# delay_calibrator.net
KiCad netlist of a schematic drawn in EAGLE
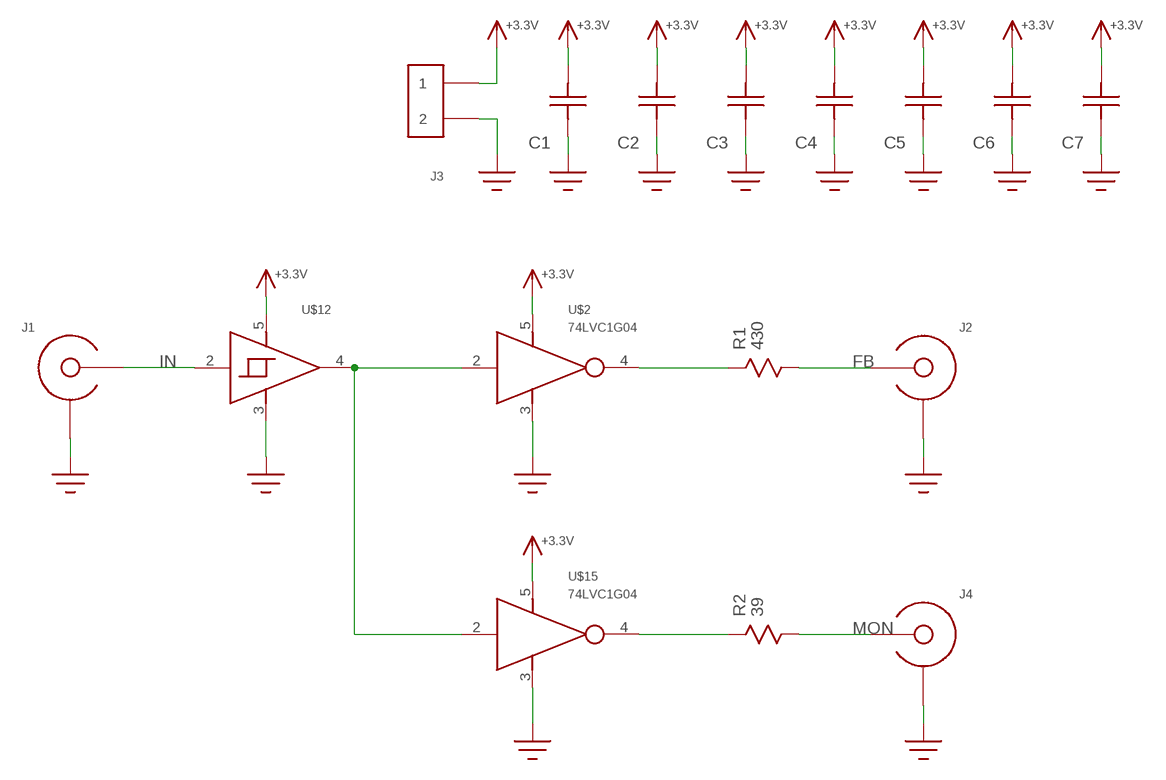
[diagram p0: schematic, sheet 1]

(export (version "E")
  (design (tool "Eeschema 10.0.6"))
  (components
    (comp (ref "C1")
      (value "C1206")
      (footprint "eagle-import:1206")
      (libsource (lib "eagle-import") (part "C1206"))
    )
    (comp (ref "C2")
      (value "C0603")
      (footprint "eagle-import:C0603")
      (libsource (lib "eagle-import") (part "C0603"))
    )
    (comp (ref "C3")
      (value "C0603")
      (footprint "eagle-import:C0603")
      (libsource (lib "eagle-import") (part "C0603"))
    )
    (comp (ref "C4")
      (value "C0603")
      (footprint "eagle-import:C0603")
      (libsource (lib "eagle-import") (part "C0603"))
    )
    (comp (ref "C5")
      (value "C0603")
      (footprint "eagle-import:C0603")
      (libsource (lib "eagle-import") (part "C0603"))
    )
    (comp (ref "C6")
      (value "C0603")
      (footprint "eagle-import:C0603")
      (libsource (lib "eagle-import") (part "C0603"))
    )
    (comp (ref "C7")
      (value "C0603")
      (footprint "eagle-import:C0603")
      (libsource (lib "eagle-import") (part "C0603"))
    )
    (comp (ref "J1")
      (value "EDGE_LAUNCH_JACK")
      (footprint "eagle-import:EDGE_LAUNCH_RF_CON")
      (libsource (lib "eagle-import") (part "EDGE_LAUNCH_JACK"))
    )
    (comp (ref "J2")
      (value "EDGE_LAUNCH_JACK")
      (footprint "eagle-import:EDGE_LAUNCH_RF_CON")
      (libsource (lib "eagle-import") (part "EDGE_LAUNCH_JACK"))
    )
    (comp (ref "J3")
      (value "HEADER_2PIN")
      (footprint "eagle-import:HEADER_2PIN")
      (libsource (lib "eagle-import") (part "HEADER_2PIN"))
    )
    (comp (ref "J4")
      (value "EDGE_LAUNCH_JACK")
      (footprint "eagle-import:EDGE_LAUNCH_RF_CON")
      (libsource (lib "eagle-import") (part "EDGE_LAUNCH_JACK"))
    )
    (comp (ref "R1")
      (value "430")
      (footprint "eagle-import:R0603")
      (libsource (lib "eagle-import") (part "R0603"))
    )
    (comp (ref "R2")
      (value "39")
      (footprint "eagle-import:R0603")
      (libsource (lib "eagle-import") (part "R0603"))
    )
    (comp (ref "U$2")
      (value "74LVC1G04")
      (footprint "eagle-import:SOT23-5")
      (libsource (lib "eagle-import") (part "74LVC1G04"))
    )
    (comp (ref "U$12")
      (value "74LVC1G17")
      (footprint "eagle-import:SOT23-5")
      (libsource (lib "eagle-import") (part "74LVC1G17"))
    )
    (comp (ref "U$15")
      (value "74LVC1G04")
      (footprint "eagle-import:SOT23-5")
      (libsource (lib "eagle-import") (part "74LVC1G04"))
    )
  )
  (nets
    (net (code "1") (name "+3.3V") (class "Default")
      (node (ref "C1") (pin "P$1") (pinfunction "P$1_P$1") (pintype "bidirectional"))
      (node (ref "C2") (pin "P$1") (pinfunction "P$1_P$1") (pintype "bidirectional"))
      (node (ref "C3") (pin "P$1") (pinfunction "P$1_P$1") (pintype "bidirectional"))
      (node (ref "C4") (pin "P$1") (pinfunction "P$1_P$1") (pintype "bidirectional"))
      (node (ref "C5") (pin "P$1") (pinfunction "P$1_P$1") (pintype "bidirectional"))
      (node (ref "C6") (pin "P$1") (pinfunction "P$1_P$1") (pintype "bidirectional"))
      (node (ref "C7") (pin "P$1") (pinfunction "P$1_P$1") (pintype "bidirectional"))
      (node (ref "J3") (pin "1") (pinfunction "1_1") (pintype "bidirectional"))
      (node (ref "U$12") (pin "5") (pinfunction "VCC_5") (pintype "bidirectional"))
      (node (ref "U$15") (pin "5") (pinfunction "VCC_5") (pintype "bidirectional"))
      (node (ref "U$2") (pin "5") (pinfunction "VCC_5") (pintype "bidirectional"))
    )
    (net (code "2") (name "/FB") (class "Default")
      (node (ref "J2") (pin "CENTER") (pinfunction "CENTER_CENTER") (pintype "bidirectional"))
      (node (ref "R1") (pin "P$2") (pinfunction "P$4_P$2") (pintype "bidirectional"))
    )
    (net (code "3") (name "/IN") (class "Default")
      (node (ref "J1") (pin "CENTER") (pinfunction "CENTER_CENTER") (pintype "bidirectional"))
      (node (ref "U$12") (pin "2") (pinfunction "IN_2") (pintype "bidirectional"))
    )
    (net (code "4") (name "/MON") (class "Default")
      (node (ref "J4") (pin "CENTER") (pinfunction "CENTER_CENTER") (pintype "bidirectional"))
      (node (ref "R2") (pin "P$2") (pinfunction "P$4_P$2") (pintype "bidirectional"))
    )
    (net (code "5") (name "GND") (class "Default")
      (node (ref "C1") (pin "P$2") (pinfunction "P$2_P$2") (pintype "bidirectional"))
      (node (ref "C2") (pin "P$2") (pinfunction "P$2_P$2") (pintype "bidirectional"))
      (node (ref "C3") (pin "P$2") (pinfunction "P$2_P$2") (pintype "bidirectional"))
      (node (ref "C4") (pin "P$2") (pinfunction "P$2_P$2") (pintype "bidirectional"))
      (node (ref "C5") (pin "P$2") (pinfunction "P$2_P$2") (pintype "bidirectional"))
      (node (ref "C6") (pin "P$2") (pinfunction "P$2_P$2") (pintype "bidirectional"))
      (node (ref "C7") (pin "P$2") (pinfunction "P$2_P$2") (pintype "bidirectional"))
      (node (ref "J1") (pin "GND@1") (pinfunction "SHIELD_GND@1") (pintype "bidirectional"))
      (node (ref "J1") (pin "GND@10") (pinfunction "SHIELD_GND@10") (pintype "bidirectional"))
      (node (ref "J1") (pin "GND@11") (pinfunction "SHIELD_GND@11") (pintype "bidirectional"))
      (node (ref "J1") (pin "GND@12") (pinfunction "SHIELD_GND@12") (pintype "bidirectional"))
      (node (ref "J1") (pin "GND@2") (pinfunction "SHIELD_GND@2") (pintype "bidirectional"))
      (node (ref "J1") (pin "GND@3") (pinfunction "SHIELD_GND@3") (pintype "bidirectional"))
      (node (ref "J1") (pin "GND@4") (pinfunction "SHIELD_GND@4") (pintype "bidirectional"))
      (node (ref "J1") (pin "GND@5") (pinfunction "SHIELD_GND@5") (pintype "bidirectional"))
      (node (ref "J1") (pin "GND@6") (pinfunction "SHIELD_GND@6") (pintype "bidirectional"))
      (node (ref "J1") (pin "GND@7") (pinfunction "SHIELD_GND@7") (pintype "bidirectional"))
      (node (ref "J1") (pin "GND@8") (pinfunction "SHIELD_GND@8") (pintype "bidirectional"))
      (node (ref "J1") (pin "GND@9") (pinfunction "SHIELD_GND@9") (pintype "bidirectional"))
      (node (ref "J1") (pin "SHIELD@1") (pinfunction "SHIELD_SHIELD@1") (pintype "bidirectional"))
      (node (ref "J1") (pin "SHIELD@2") (pinfunction "SHIELD_SHIELD@2") (pintype "bidirectional"))
      (node (ref "J2") (pin "GND@1") (pinfunction "SHIELD_GND@1") (pintype "bidirectional"))
      (node (ref "J2") (pin "GND@10") (pinfunction "SHIELD_GND@10") (pintype "bidirectional"))
      (node (ref "J2") (pin "GND@11") (pinfunction "SHIELD_GND@11") (pintype "bidirectional"))
      (node (ref "J2") (pin "GND@12") (pinfunction "SHIELD_GND@12") (pintype "bidirectional"))
      (node (ref "J2") (pin "GND@2") (pinfunction "SHIELD_GND@2") (pintype "bidirectional"))
      (node (ref "J2") (pin "GND@3") (pinfunction "SHIELD_GND@3") (pintype "bidirectional"))
      (node (ref "J2") (pin "GND@4") (pinfunction "SHIELD_GND@4") (pintype "bidirectional"))
      (node (ref "J2") (pin "GND@5") (pinfunction "SHIELD_GND@5") (pintype "bidirectional"))
      (node (ref "J2") (pin "GND@6") (pinfunction "SHIELD_GND@6") (pintype "bidirectional"))
      (node (ref "J2") (pin "GND@7") (pinfunction "SHIELD_GND@7") (pintype "bidirectional"))
      (node (ref "J2") (pin "GND@8") (pinfunction "SHIELD_GND@8") (pintype "bidirectional"))
      (node (ref "J2") (pin "GND@9") (pinfunction "SHIELD_GND@9") (pintype "bidirectional"))
      (node (ref "J2") (pin "SHIELD@1") (pinfunction "SHIELD_SHIELD@1") (pintype "bidirectional"))
      (node (ref "J2") (pin "SHIELD@2") (pinfunction "SHIELD_SHIELD@2") (pintype "bidirectional"))
      (node (ref "J3") (pin "2") (pinfunction "2_2") (pintype "bidirectional"))
      (node (ref "J4") (pin "GND@1") (pinfunction "SHIELD_GND@1") (pintype "bidirectional"))
      (node (ref "J4") (pin "GND@10") (pinfunction "SHIELD_GND@10") (pintype "bidirectional"))
      (node (ref "J4") (pin "GND@11") (pinfunction "SHIELD_GND@11") (pintype "bidirectional"))
      (node (ref "J4") (pin "GND@12") (pinfunction "SHIELD_GND@12") (pintype "bidirectional"))
      (node (ref "J4") (pin "GND@2") (pinfunction "SHIELD_GND@2") (pintype "bidirectional"))
      (node (ref "J4") (pin "GND@3") (pinfunction "SHIELD_GND@3") (pintype "bidirectional"))
      (node (ref "J4") (pin "GND@4") (pinfunction "SHIELD_GND@4") (pintype "bidirectional"))
      (node (ref "J4") (pin "GND@5") (pinfunction "SHIELD_GND@5") (pintype "bidirectional"))
      (node (ref "J4") (pin "GND@6") (pinfunction "SHIELD_GND@6") (pintype "bidirectional"))
      (node (ref "J4") (pin "GND@7") (pinfunction "SHIELD_GND@7") (pintype "bidirectional"))
      (node (ref "J4") (pin "GND@8") (pinfunction "SHIELD_GND@8") (pintype "bidirectional"))
      (node (ref "J4") (pin "GND@9") (pinfunction "SHIELD_GND@9") (pintype "bidirectional"))
      (node (ref "J4") (pin "SHIELD@1") (pinfunction "SHIELD_SHIELD@1") (pintype "bidirectional"))
      (node (ref "J4") (pin "SHIELD@2") (pinfunction "SHIELD_SHIELD@2") (pintype "bidirectional"))
      (node (ref "U$12") (pin "3") (pinfunction "GND_3") (pintype "bidirectional"))
      (node (ref "U$15") (pin "3") (pinfunction "GND_3") (pintype "bidirectional"))
      (node (ref "U$2") (pin "3") (pinfunction "GND_3") (pintype "bidirectional"))
    )
    (net (code "6") (name "Net-(R1-P$3)") (class "Default")
      (node (ref "R1") (pin "P$1") (pinfunction "P$3_P$1") (pintype "bidirectional"))
      (node (ref "U$2") (pin "4") (pinfunction "OUT_4") (pintype "bidirectional"))
    )
    (net (code "7") (name "Net-(R2-P$3)") (class "Default")
      (node (ref "R2") (pin "P$1") (pinfunction "P$3_P$1") (pintype "bidirectional"))
      (node (ref "U$15") (pin "4") (pinfunction "OUT_4") (pintype "bidirectional"))
    )
    (net (code "8") (name "Net-(U$12-OUT)") (class "Default")
      (node (ref "U$12") (pin "4") (pinfunction "OUT_4") (pintype "bidirectional"))
      (node (ref "U$15") (pin "2") (pinfunction "IN_2") (pintype "bidirectional"))
      (node (ref "U$2") (pin "2") (pinfunction "IN_2") (pintype "bidirectional"))
    )
  )
)
